# rtm-top.net
KiCad netlist of a schematic drawn in Altium Designer
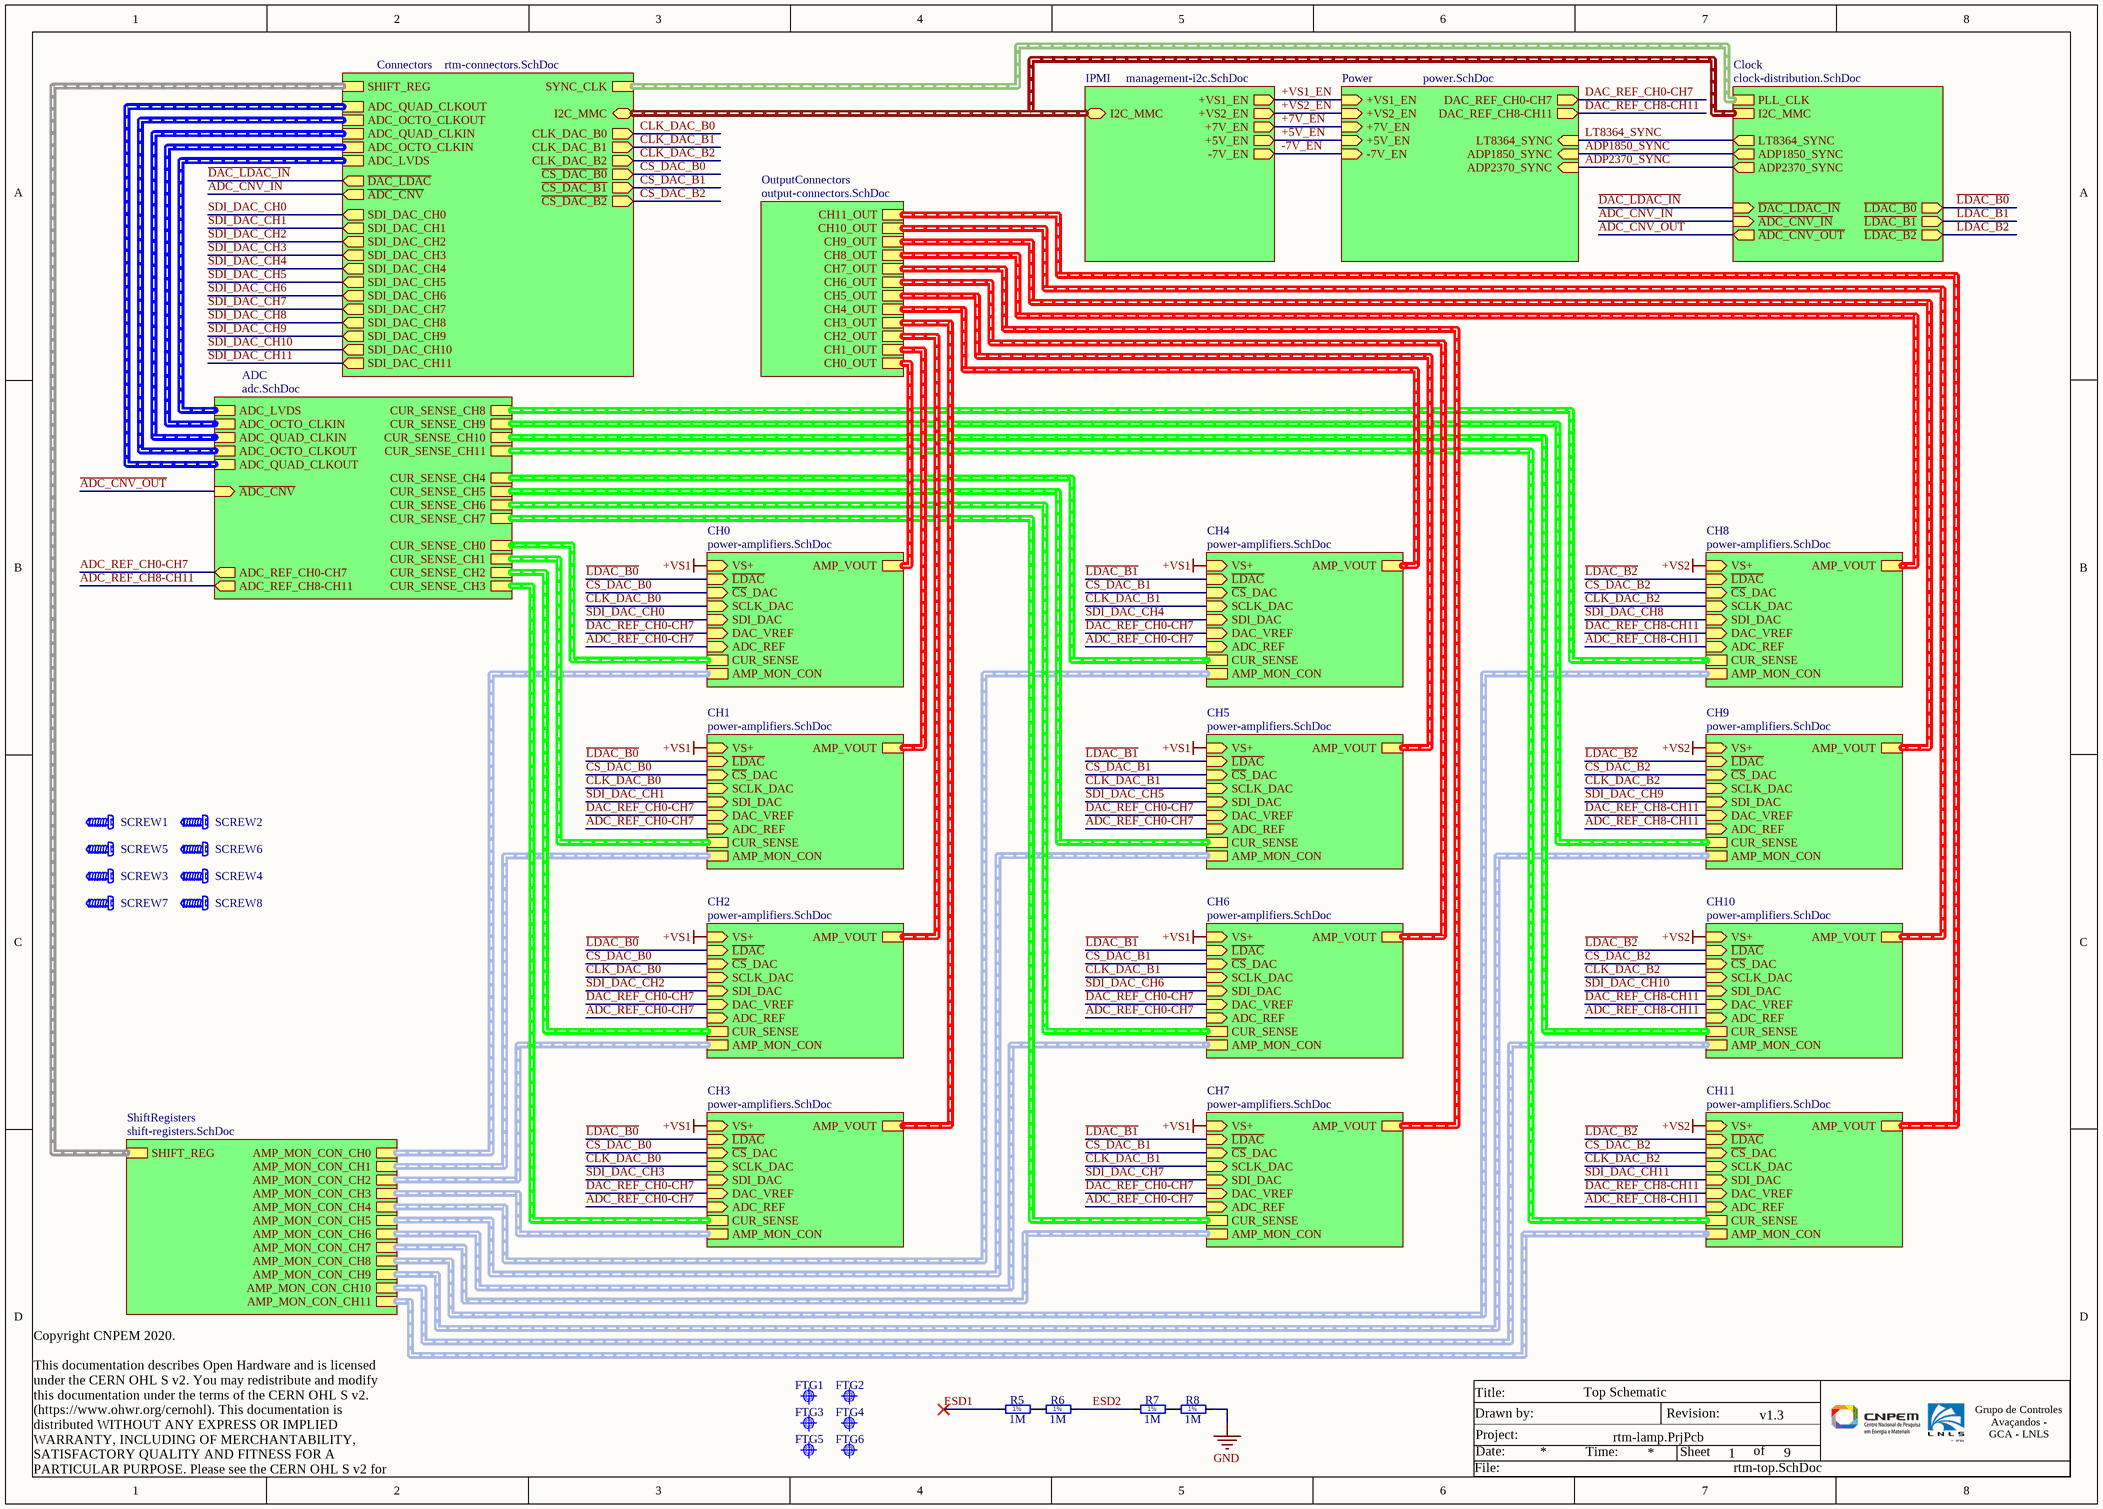
[diagram p0: rtm-top.SchDoc]

(export (version "E")
  (design (tool "Eeschema 10.0.6"))
  (components
    (comp (ref "FTG1")
      (value "Use only in PCB")
      (footprint "FIDUCIAL_TOP_C100-200")
      (description "Round Fiducial Target, Top Layer, 1.0mm, Top Solder 2.0mm, Keepout =2.0mm")
      (fields (field (name "PART NUMBER") "FIDUCIAL_TARGET_C100-200") (field (name "AUTHOR") "CERN DEM JLC"))
      (libsource (lib "Eletro-mechanical") (part "Fiducial Target"))
    )
    (comp (ref "FTG2")
      (value "Use only in PCB")
      (footprint "FIDUCIAL_TOP_C100-200")
      (description "Round Fiducial Target, Top Layer, 1.0mm, Top Solder 2.0mm, Keepout =2.0mm")
      (fields (field (name "PART NUMBER") "FIDUCIAL_TARGET_C100-200") (field (name "AUTHOR") "CERN DEM JLC"))
      (libsource (lib "Eletro-mechanical") (part "Fiducial Target"))
    )
    (comp (ref "FTG3")
      (value "Use only in PCB")
      (footprint "FIDUCIAL_TOP_C100-200")
      (description "Round Fiducial Target, Top Layer, 1.0mm, Top Solder 2.0mm, Keepout =2.0mm")
      (fields (field (name "PART NUMBER") "FIDUCIAL_TARGET_C100-200") (field (name "AUTHOR") "CERN DEM JLC"))
      (libsource (lib "Eletro-mechanical") (part "Fiducial Target"))
    )
    (comp (ref "FTG4")
      (value "Use only in PCB")
      (footprint "FIDUCIAL_TOP_C100-200")
      (description "Round Fiducial Target, Top Layer, 1.0mm, Top Solder 2.0mm, Keepout =2.0mm")
      (fields (field (name "PART NUMBER") "FIDUCIAL_TARGET_C100-200") (field (name "AUTHOR") "CERN DEM JLC"))
      (libsource (lib "Eletro-mechanical") (part "Fiducial Target"))
    )
    (comp (ref "FTG5")
      (value "Use only in PCB")
      (footprint "FIDUCIAL_TOP_C100-200")
      (description "Round Fiducial Target, Top Layer, 1.0mm, Top Solder 2.0mm, Keepout =2.0mm")
      (fields (field (name "PART NUMBER") "FIDUCIAL_TARGET_C100-200") (field (name "AUTHOR") "CERN DEM JLC"))
      (libsource (lib "Eletro-mechanical") (part "Fiducial Target"))
    )
    (comp (ref "FTG6")
      (value "Use only in PCB")
      (footprint "FIDUCIAL_TOP_C100-200")
      (description "Round Fiducial Target, Top Layer, 1.0mm, Top Solder 2.0mm, Keepout =2.0mm")
      (fields (field (name "PART NUMBER") "FIDUCIAL_TARGET_C100-200") (field (name "AUTHOR") "CERN DEM JLC"))
      (libsource (lib "Eletro-mechanical") (part "Fiducial Target"))
    )
    (comp (ref "R5")
      (value "1M")
      (footprint "RESC3216X65N")
      (description "General Purpose Thick Film Chip Resistor")
      (fields
        (field (name "PART NUMBER") "R1206_1M_1%_0.25W_100PPM")
        (field (name "POWER") "0.25W")
        (field (name "AUTHOR") "CERN DEM JLC")
      )
      (libsource (lib "Resistors") (part "Resistor - 1%"))
    )
    (comp (ref "R6")
      (value "1M")
      (footprint "RESC3216X65N")
      (description "General Purpose Thick Film Chip Resistor")
      (fields
        (field (name "PART NUMBER") "R1206_1M_1%_0.25W_100PPM")
        (field (name "POWER") "0.25W")
        (field (name "AUTHOR") "CERN DEM JLC")
      )
      (libsource (lib "Resistors") (part "Resistor - 1%"))
    )
    (comp (ref "R7")
      (value "1M")
      (footprint "RESC3216X65N")
      (description "General Purpose Thick Film Chip Resistor")
      (fields
        (field (name "PART NUMBER") "R1206_1M_1%_0.25W_100PPM")
        (field (name "POWER") "0.25W")
        (field (name "AUTHOR") "CERN DEM JLC")
      )
      (libsource (lib "Resistors") (part "Resistor - 1%"))
    )
    (comp (ref "R8")
      (value "1M")
      (footprint "RESC3216X65N")
      (description "General Purpose Thick Film Chip Resistor")
      (fields
        (field (name "PART NUMBER") "R1206_1M_1%_0.25W_100PPM")
        (field (name "POWER") "0.25W")
        (field (name "AUTHOR") "CERN DEM JLC")
      )
      (libsource (lib "Resistors") (part "Resistor - 1%"))
    )
    (comp (ref "SCREW1")
      (value "M2x6")
      (footprint "MCMASTERCARR_90910A922_V")
      (description "M2 L=6mm Torx Socket Pan Head Screw, Fully Threaded - Stainless Steel")
      (fields
        (field (name "PART NUMBER") "MCMASTERCARR_90910A922_v")
        (field (name "MANUFACTURER") "MCMASTER-CARR")
        (field (name "AUTHOR") "LNLS DIG AFG")
      )
      (libsource (lib "Eletro-mechanical_LNLS") (part "Screw"))
    )
    (comp (ref "SCREW2")
      (value "M2x6")
      (footprint "MCMASTERCARR_90910A922_V")
      (description "M2 L=6mm Torx Socket Pan Head Screw, Fully Threaded - Stainless Steel")
      (fields
        (field (name "PART NUMBER") "MCMASTERCARR_90910A922_v")
        (field (name "MANUFACTURER") "MCMASTER-CARR")
        (field (name "AUTHOR") "LNLS DIG AFG")
      )
      (libsource (lib "Eletro-mechanical_LNLS") (part "Screw"))
    )
    (comp (ref "SCREW3")
      (value "M2x6")
      (footprint "MCMASTERCARR_90910A922_V")
      (description "M2 L=6mm Torx Socket Pan Head Screw, Fully Threaded - Stainless Steel")
      (fields
        (field (name "PART NUMBER") "MCMASTERCARR_90910A922_v")
        (field (name "MANUFACTURER") "MCMASTER-CARR")
        (field (name "AUTHOR") "LNLS DIG AFG")
      )
      (libsource (lib "Eletro-mechanical_LNLS") (part "Screw"))
    )
    (comp (ref "SCREW4")
      (value "M2x6")
      (footprint "MCMASTERCARR_90910A922_V")
      (description "M2 L=6mm Torx Socket Pan Head Screw, Fully Threaded - Stainless Steel")
      (fields
        (field (name "PART NUMBER") "MCMASTERCARR_90910A922_v")
        (field (name "MANUFACTURER") "MCMASTER-CARR")
        (field (name "AUTHOR") "LNLS DIG AFG")
      )
      (libsource (lib "Eletro-mechanical_LNLS") (part "Screw"))
    )
    (comp (ref "SCREW5")
      (value "M2x6")
      (footprint "MCMASTERCARR_90910A922_V")
      (description "M2 L=6mm Torx Socket Pan Head Screw, Fully Threaded - Stainless Steel")
      (fields
        (field (name "PART NUMBER") "MCMASTERCARR_90910A922_v")
        (field (name "MANUFACTURER") "MCMASTER-CARR")
        (field (name "AUTHOR") "LNLS DIG AFG")
      )
      (libsource (lib "Eletro-mechanical_LNLS") (part "Screw"))
    )
    (comp (ref "SCREW6")
      (value "M2x6")
      (footprint "MCMASTERCARR_90910A922_V")
      (description "M2 L=6mm Torx Socket Pan Head Screw, Fully Threaded - Stainless Steel")
      (fields
        (field (name "PART NUMBER") "MCMASTERCARR_90910A922_v")
        (field (name "MANUFACTURER") "MCMASTER-CARR")
        (field (name "AUTHOR") "LNLS DIG AFG")
      )
      (libsource (lib "Eletro-mechanical_LNLS") (part "Screw"))
    )
    (comp (ref "SCREW7")
      (value "M2x6")
      (footprint "MCMASTERCARR_90910A922_V")
      (description "M2 L=6mm Torx Socket Pan Head Screw, Fully Threaded - Stainless Steel")
      (fields
        (field (name "PART NUMBER") "MCMASTERCARR_90910A922_v")
        (field (name "MANUFACTURER") "MCMASTER-CARR")
        (field (name "AUTHOR") "LNLS DIG AFG")
      )
      (libsource (lib "Eletro-mechanical_LNLS") (part "Screw"))
    )
    (comp (ref "SCREW8")
      (value "M2x6")
      (footprint "MCMASTERCARR_90910A922_V")
      (description "M2 L=6mm Torx Socket Pan Head Screw, Fully Threaded - Stainless Steel")
      (fields
        (field (name "PART NUMBER") "MCMASTERCARR_90910A922_v")
        (field (name "MANUFACTURER") "MCMASTER-CARR")
        (field (name "AUTHOR") "LNLS DIG AFG")
      )
      (libsource (lib "Eletro-mechanical_LNLS") (part "Screw"))
    )
  )
  (nets
    (net (code "58") (name "/ESD1") (class "Default")
      (node (ref "R5") (pin "1") (pinfunction "1_1") (pintype "passive+no_connect"))
    )
    (net (code "59") (name "/ESD2") (class "Default")
      (node (ref "R6") (pin "2") (pinfunction "2_2") (pintype "passive"))
      (node (ref "R7") (pin "1") (pinfunction "1_1") (pintype "passive"))
    )
    (net (code "85") (name "GND") (class "Default")
      (node (ref "R8") (pin "2") (pinfunction "2_2") (pintype "passive"))
    )
    (net (code "86") (name "Net-(R5-Pad2)") (class "Default")
      (node (ref "R5") (pin "2") (pinfunction "2_2") (pintype "passive"))
      (node (ref "R6") (pin "1") (pinfunction "1_1") (pintype "passive"))
    )
    (net (code "87") (name "Net-(R7-Pad2)") (class "Default")
      (node (ref "R7") (pin "2") (pinfunction "2_2") (pintype "passive"))
      (node (ref "R8") (pin "1") (pinfunction "1_1") (pintype "passive"))
    )
  )
)
